# Board_1.net
KiCad netlist of a schematic drawn in EAGLE
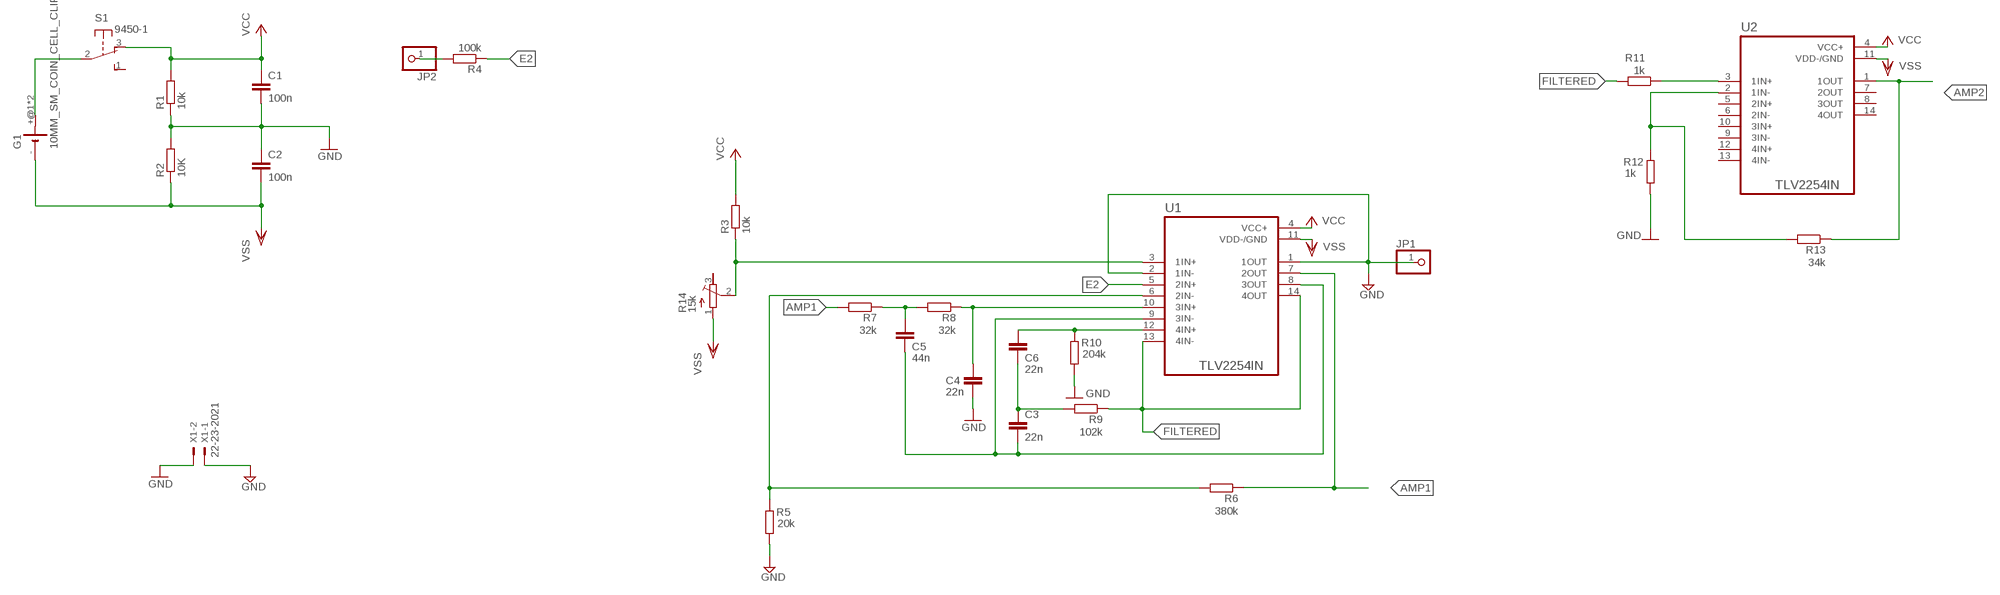
[diagram p0: schematic, sheet 1]

(export (version "E")
  (design (tool "Eeschema 10.0.6"))
  (components
    (comp (ref "C1")
      (value "100n")
      (footprint "eagle-import:C0805")
      (libsource (lib "eagle-import") (part "C-EUC0805"))
    )
    (comp (ref "C2")
      (value "100n")
      (footprint "eagle-import:C0805")
      (libsource (lib "eagle-import") (part "C-EUC0805"))
    )
    (comp (ref "C3")
      (value "22n")
      (footprint "eagle-import:C0805")
      (libsource (lib "eagle-import") (part "C-EUC0805"))
    )
    (comp (ref "C4")
      (value "22n")
      (footprint "eagle-import:C0805")
      (libsource (lib "eagle-import") (part "C-EUC0805"))
    )
    (comp (ref "C5")
      (value "44n")
      (footprint "eagle-import:C0805")
      (libsource (lib "eagle-import") (part "C-EUC0805"))
    )
    (comp (ref "C6")
      (value "22n")
      (footprint "eagle-import:C0805")
      (libsource (lib "eagle-import") (part "C-EUC0805"))
    )
    (comp (ref "G1")
      (value "10MM_SM_COIN_CELL_CLIP")
      (footprint "eagle-import:10MM_SM_COIN_CELL_CLIP")
      (libsource (lib "eagle-import") (part "10MM_SM_COIN_CELL_CLIP"))
    )
    (comp (ref "JP1")
      (value "PINHD-1X1")
      (footprint "eagle-import:1X01")
      (libsource (lib "eagle-import") (part "PINHD-1X1"))
    )
    (comp (ref "JP2")
      (value "PINHD-1X1")
      (footprint "eagle-import:1X01")
      (libsource (lib "eagle-import") (part "PINHD-1X1"))
    )
    (comp (ref "R1")
      (value "10k")
      (footprint "eagle-import:R0805")
      (libsource (lib "eagle-import") (part "R-EU_R0805"))
    )
    (comp (ref "R2")
      (value "10K")
      (footprint "eagle-import:R0805")
      (libsource (lib "eagle-import") (part "R-EU_R0805"))
    )
    (comp (ref "R3")
      (value "10k")
      (footprint "eagle-import:R0805")
      (libsource (lib "eagle-import") (part "R-EU_R0805"))
    )
    (comp (ref "R4")
      (value "100k")
      (footprint "eagle-import:R0805")
      (libsource (lib "eagle-import") (part "R-EU_R0805"))
    )
    (comp (ref "R5")
      (value "20k")
      (footprint "eagle-import:R0805")
      (libsource (lib "eagle-import") (part "R-EU_R0805"))
    )
    (comp (ref "R6")
      (value "380k")
      (footprint "eagle-import:R0805")
      (libsource (lib "eagle-import") (part "R-EU_R0805"))
    )
    (comp (ref "R7")
      (value "32k")
      (footprint "eagle-import:R0805")
      (libsource (lib "eagle-import") (part "R-EU_R0805"))
    )
    (comp (ref "R8")
      (value "32k")
      (footprint "eagle-import:R0805")
      (libsource (lib "eagle-import") (part "R-EU_R0805"))
    )
    (comp (ref "R9")
      (value "102k")
      (footprint "eagle-import:R0805")
      (libsource (lib "eagle-import") (part "R-EU_R0805"))
    )
    (comp (ref "R10")
      (value "204k")
      (footprint "eagle-import:R0805")
      (libsource (lib "eagle-import") (part "R-EU_R0805"))
    )
    (comp (ref "R11")
      (value "1k")
      (footprint "eagle-import:R0805")
      (libsource (lib "eagle-import") (part "R-EU_R0805"))
    )
    (comp (ref "R12")
      (value "1k")
      (footprint "eagle-import:R0805")
      (libsource (lib "eagle-import") (part "R-EU_R0805"))
    )
    (comp (ref "R13")
      (value "34k")
      (footprint "eagle-import:R0805")
      (libsource (lib "eagle-import") (part "R-EU_R0805"))
    )
    (comp (ref "R14")
      (value "15k")
      (footprint "eagle-import:RTRIM4G_J")
      (libsource (lib "eagle-import") (part "R-TRIMM4G/J"))
    )
    (comp (ref "S1")
      (value "9450-1")
      (footprint "eagle-import:9450-1")
      (libsource (lib "eagle-import") (part "9450-1"))
    )
    (comp (ref "U1")
      (value "TLV2254IN")
      (footprint "eagle-import:DIP794W45P254L1969H508Q14")
      (fields (field (name "MF") "Texas Instruments"))
      (libsource (lib "eagle-import") (part "TLV2254IN"))
    )
    (comp (ref "U2")
      (value "TLV2254IN")
      (footprint "eagle-import:DIP794W45P254L1969H508Q14")
      (fields (field (name "MF") "Texas Instruments"))
      (libsource (lib "eagle-import") (part "TLV2254IN"))
    )
    (comp (ref "X1")
      (value "22-23-2021")
      (footprint "eagle-import:22-23-2021")
      (fields (field (name "MF") "MOLEX"))
      (libsource (lib "eagle-import") (part "22-23-2021"))
    )
  )
  (nets
    (net (code "1") (name "AMP1") (class "Default")
      (node (ref "R6") (pin "1") (pinfunction "1_1") (pintype "passive"))
      (node (ref "R7") (pin "2") (pinfunction "2_2") (pintype "passive"))
      (node (ref "U1") (pin "7") (pinfunction "2OUT_7") (pintype "output"))
    )
    (net (code "2") (name "AMP2") (class "Default")
      (node (ref "R13") (pin "1") (pinfunction "1_1") (pintype "passive"))
      (node (ref "U2") (pin "1") (pinfunction "1OUT_1") (pintype "output"))
    )
    (net (code "3") (name "E2") (class "Default")
      (node (ref "R4") (pin "1") (pinfunction "1_1") (pintype "passive"))
      (node (ref "U1") (pin "5") (pinfunction "2IN+_5") (pintype "input"))
    )
    (net (code "4") (name "FILTERED") (class "Default")
      (node (ref "R11") (pin "2") (pinfunction "2_2") (pintype "passive"))
      (node (ref "R9") (pin "1") (pinfunction "1_1") (pintype "passive"))
      (node (ref "U1") (pin "13") (pinfunction "4IN-_13") (pintype "input"))
      (node (ref "U1") (pin "14") (pinfunction "4OUT_14") (pintype "output"))
    )
    (net (code "5") (name "GND") (class "Default")
      (node (ref "C1") (pin "2") (pinfunction "2_2") (pintype "passive"))
      (node (ref "C2") (pin "1") (pinfunction "1_1") (pintype "passive"))
      (node (ref "C4") (pin "2") (pinfunction "2_2") (pintype "passive"))
      (node (ref "JP1") (pin "1") (pinfunction "1_1") (pintype "passive"))
      (node (ref "R1") (pin "1") (pinfunction "1_1") (pintype "passive"))
      (node (ref "R10") (pin "2") (pinfunction "2_2") (pintype "passive"))
      (node (ref "R12") (pin "2") (pinfunction "2_2") (pintype "passive"))
      (node (ref "R2") (pin "2") (pinfunction "2_2") (pintype "passive"))
      (node (ref "R5") (pin "2") (pinfunction "2_2") (pintype "passive"))
      (node (ref "U1") (pin "1") (pinfunction "1OUT_1") (pintype "output"))
      (node (ref "U1") (pin "2") (pinfunction "1IN-_2") (pintype "input"))
      (node (ref "X1") (pin "1") (pinfunction "S_1") (pintype "passive"))
      (node (ref "X1") (pin "2") (pinfunction "S_2") (pintype "passive"))
    )
    (net (code "6") (name "Net-(C3-Pad1)") (class "Default")
      (node (ref "C3") (pin "1") (pinfunction "1_1") (pintype "passive"))
      (node (ref "C6") (pin "2") (pinfunction "2_2") (pintype "passive"))
      (node (ref "R9") (pin "2") (pinfunction "2_2") (pintype "passive"))
    )
    (net (code "7") (name "Net-(C5-Pad1)") (class "Default")
      (node (ref "C5") (pin "1") (pinfunction "1_1") (pintype "passive"))
      (node (ref "R7") (pin "1") (pinfunction "1_1") (pintype "passive"))
      (node (ref "R8") (pin "2") (pinfunction "2_2") (pintype "passive"))
    )
    (net (code "8") (name "Net-(JP2-Pad1)") (class "Default")
      (node (ref "JP2") (pin "1") (pinfunction "1_1") (pintype "passive"))
      (node (ref "R4") (pin "2") (pinfunction "2_2") (pintype "passive"))
    )
    (net (code "9") (name "Net-(R14-S)") (class "Default")
      (node (ref "R14") (pin "2") (pinfunction "S_2") (pintype "passive"))
      (node (ref "R3") (pin "1") (pinfunction "1_1") (pintype "passive"))
      (node (ref "U1") (pin "3") (pinfunction "1IN+_3") (pintype "input"))
    )
    (net (code "10") (name "Net-(S1-P)") (class "Default")
      (node (ref "G1") (pin "+@1") (pinfunction "+_+@1") (pintype "passive"))
      (node (ref "G1") (pin "+@2") (pinfunction "+_+@2") (pintype "passive"))
      (node (ref "S1") (pin "2") (pinfunction "P_2") (pintype "passive"))
    )
    (net (code "11") (name "Net-(U1-2IN-)") (class "Default")
      (node (ref "R5") (pin "1") (pinfunction "1_1") (pintype "passive"))
      (node (ref "R6") (pin "2") (pinfunction "2_2") (pintype "passive"))
      (node (ref "U1") (pin "6") (pinfunction "2IN-_6") (pintype "input"))
    )
    (net (code "12") (name "Net-(U1-3IN+)") (class "Default")
      (node (ref "C4") (pin "1") (pinfunction "1_1") (pintype "passive"))
      (node (ref "R8") (pin "1") (pinfunction "1_1") (pintype "passive"))
      (node (ref "U1") (pin "10") (pinfunction "3IN+_10") (pintype "input"))
    )
    (net (code "13") (name "Net-(U1-3IN-)") (class "Default")
      (node (ref "C3") (pin "2") (pinfunction "2_2") (pintype "passive"))
      (node (ref "C5") (pin "2") (pinfunction "2_2") (pintype "passive"))
      (node (ref "U1") (pin "8") (pinfunction "3OUT_8") (pintype "output"))
      (node (ref "U1") (pin "9") (pinfunction "3IN-_9") (pintype "input"))
    )
    (net (code "14") (name "Net-(U1-4IN+)") (class "Default")
      (node (ref "C6") (pin "1") (pinfunction "1_1") (pintype "passive"))
      (node (ref "R10") (pin "1") (pinfunction "1_1") (pintype "passive"))
      (node (ref "U1") (pin "12") (pinfunction "4IN+_12") (pintype "input"))
    )
    (net (code "15") (name "Net-(U2-1IN+)") (class "Default")
      (node (ref "R11") (pin "1") (pinfunction "1_1") (pintype "passive"))
      (node (ref "U2") (pin "3") (pinfunction "1IN+_3") (pintype "input"))
    )
    (net (code "16") (name "Net-(U2-1IN-)") (class "Default")
      (node (ref "R12") (pin "1") (pinfunction "1_1") (pintype "passive"))
      (node (ref "R13") (pin "2") (pinfunction "2_2") (pintype "passive"))
      (node (ref "U2") (pin "2") (pinfunction "1IN-_2") (pintype "input"))
    )
    (net (code "17") (name "VCC") (class "Default")
      (node (ref "C1") (pin "1") (pinfunction "1_1") (pintype "passive"))
      (node (ref "R1") (pin "2") (pinfunction "2_2") (pintype "passive"))
      (node (ref "R3") (pin "2") (pinfunction "2_2") (pintype "passive"))
      (node (ref "S1") (pin "3") (pinfunction "O_3") (pintype "passive"))
      (node (ref "U1") (pin "4") (pinfunction "VCC+_4") (pintype "power_in"))
      (node (ref "U2") (pin "4") (pinfunction "VCC+_4") (pintype "power_in"))
    )
    (net (code "18") (name "VSS") (class "Default")
      (node (ref "C2") (pin "2") (pinfunction "2_2") (pintype "passive"))
      (node (ref "G1") (pin "-") (pinfunction "-_-") (pintype "passive"))
      (node (ref "R14") (pin "1") (pinfunction "A_1") (pintype "passive"))
      (node (ref "R2") (pin "1") (pinfunction "1_1") (pintype "passive"))
      (node (ref "U1") (pin "11") (pinfunction "VDD-/GND_11") (pintype "power_in"))
      (node (ref "U2") (pin "11") (pinfunction "VDD-/GND_11") (pintype "power_in"))
    )
    (net (code "19") (name "unconnected-(R14-E-Pad3)") (class "Default")
      (node (ref "R14") (pin "3") (pinfunction "E_3") (pintype "passive"))
    )
    (net (code "20") (name "unconnected-(S1-S-Pad1)") (class "Default")
      (node (ref "S1") (pin "1") (pinfunction "S_1") (pintype "passive"))
    )
    (net (code "21") (name "unconnected-(U2-2IN+-Pad5)") (class "Default")
      (node (ref "U2") (pin "5") (pinfunction "2IN+_5") (pintype "input"))
    )
    (net (code "22") (name "unconnected-(U2-2IN--Pad6)") (class "Default")
      (node (ref "U2") (pin "6") (pinfunction "2IN-_6") (pintype "input"))
    )
    (net (code "23") (name "unconnected-(U2-2OUT-Pad7)") (class "Default")
      (node (ref "U2") (pin "7") (pinfunction "2OUT_7") (pintype "output"))
    )
    (net (code "24") (name "unconnected-(U2-3IN+-Pad10)") (class "Default")
      (node (ref "U2") (pin "10") (pinfunction "3IN+_10") (pintype "input"))
    )
    (net (code "25") (name "unconnected-(U2-3IN--Pad9)") (class "Default")
      (node (ref "U2") (pin "9") (pinfunction "3IN-_9") (pintype "input"))
    )
    (net (code "26") (name "unconnected-(U2-3OUT-Pad8)") (class "Default")
      (node (ref "U2") (pin "8") (pinfunction "3OUT_8") (pintype "output"))
    )
    (net (code "27") (name "unconnected-(U2-4IN+-Pad12)") (class "Default")
      (node (ref "U2") (pin "12") (pinfunction "4IN+_12") (pintype "input"))
    )
    (net (code "28") (name "unconnected-(U2-4IN--Pad13)") (class "Default")
      (node (ref "U2") (pin "13") (pinfunction "4IN-_13") (pintype "input"))
    )
    (net (code "29") (name "unconnected-(U2-4OUT-Pad14)") (class "Default")
      (node (ref "U2") (pin "14") (pinfunction "4OUT_14") (pintype "output"))
    )
  )
)
